# M_dulo_U_V_C_v_1_0.net
KiCad netlist of a schematic drawn in EAGLE
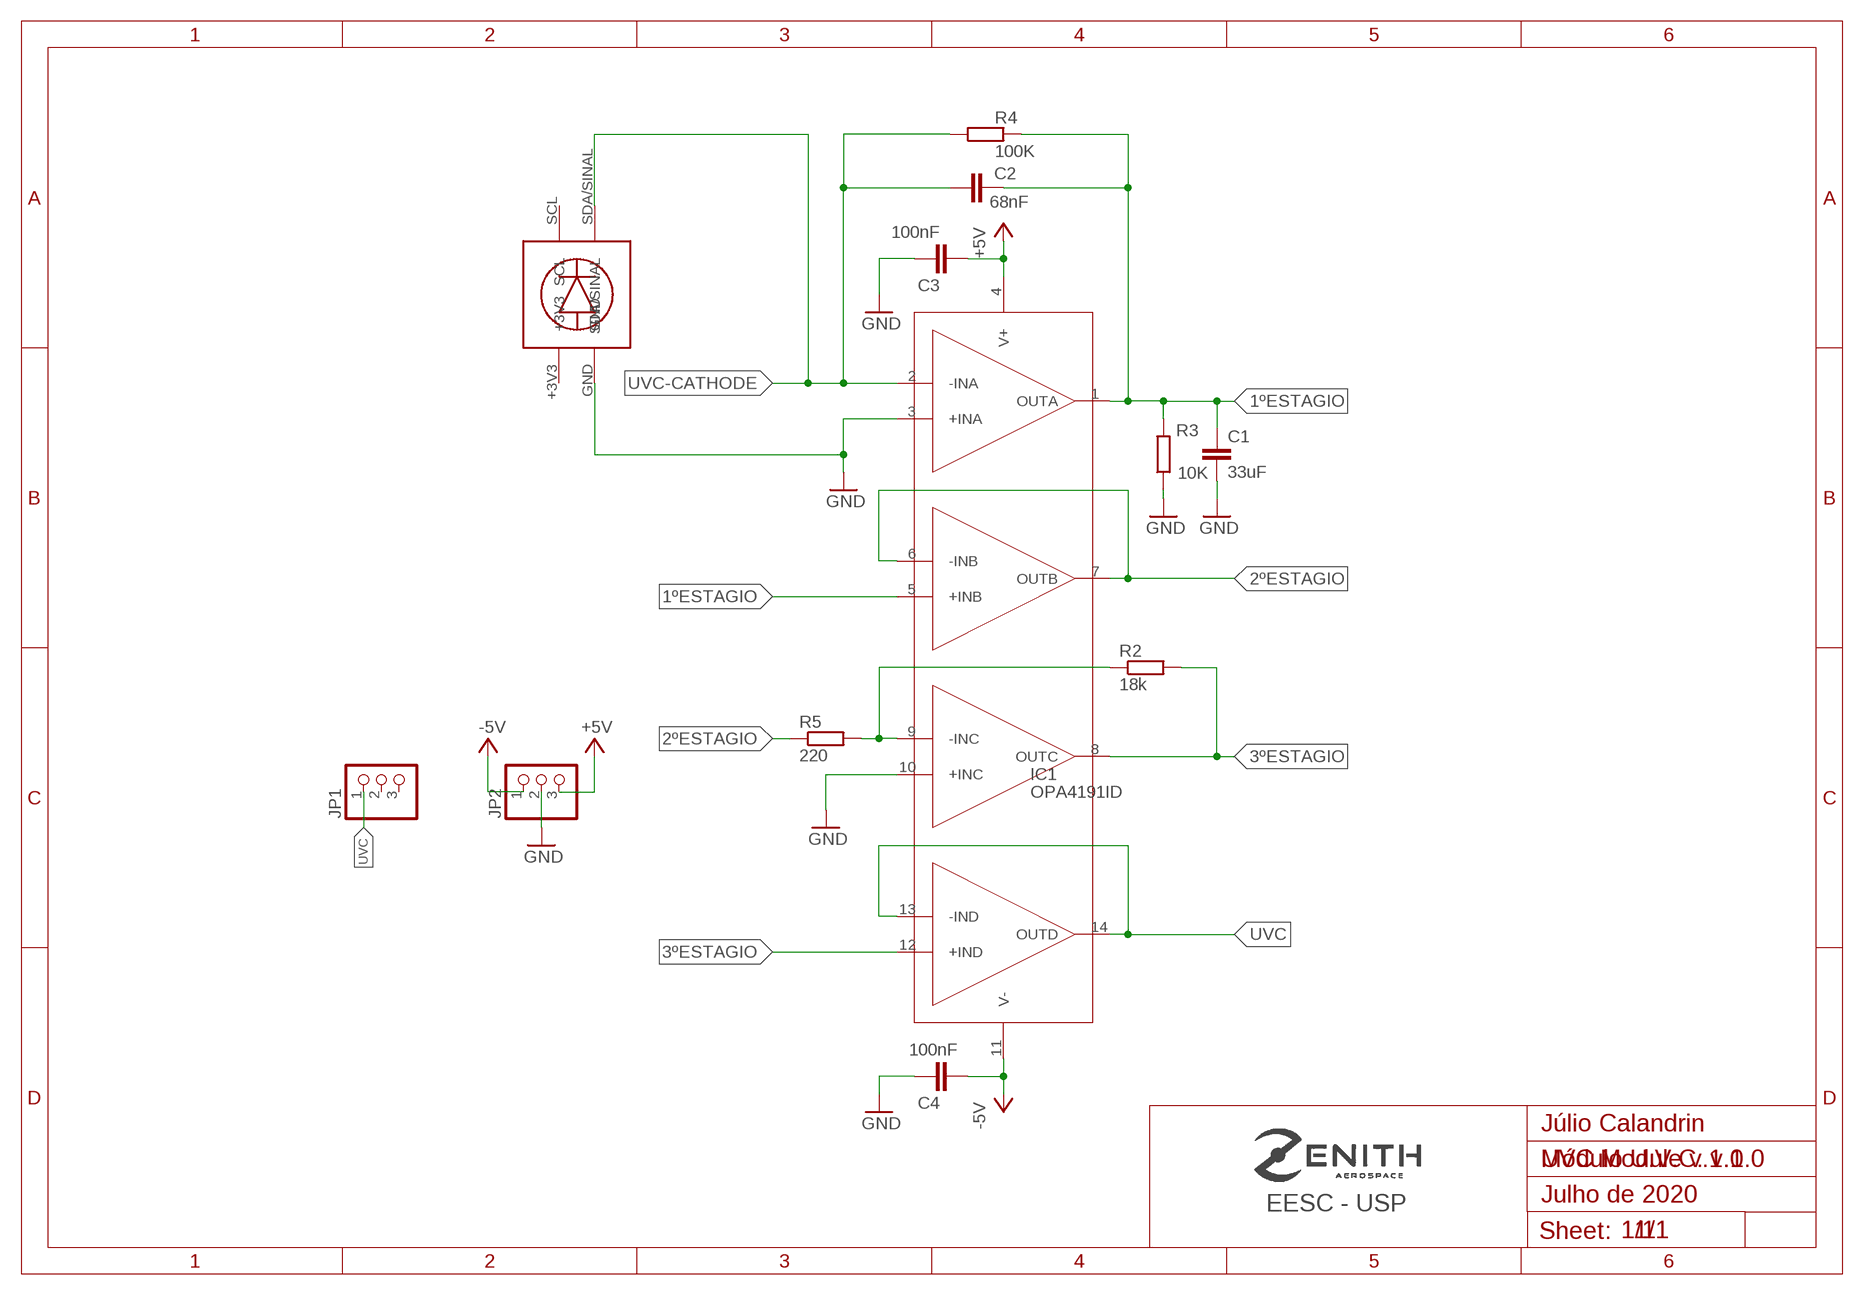
[diagram p0: schematic, sheet 1]

(export (version "E")
  (design (tool "Eeschema 10.0.6"))
  (components
    (comp (ref "C1")
      (value "33uF")
      (footprint "eagle-import:C0805")
      (libsource (lib "eagle-import") (part "C-EUC0805"))
    )
    (comp (ref "C2")
      (value "68nF")
      (footprint "eagle-import:C0805")
      (libsource (lib "eagle-import") (part "C-EUC0805"))
    )
    (comp (ref "C3")
      (value "100nF")
      (footprint "eagle-import:C0805")
      (libsource (lib "eagle-import") (part "C-EUC0805"))
    )
    (comp (ref "C4")
      (value "100nF")
      (footprint "eagle-import:C0805")
      (libsource (lib "eagle-import") (part "C-EUC0805"))
    )
    (comp (ref "IC1")
      (value "OPA4191ID")
      (footprint "eagle-import:D14_TEX")
      (fields (field (name "COPYRIGHT") "Copyright (C) 2018 Accelerated Designs. All rights reserved"))
      (libsource (lib "eagle-import") (part "OPA4191ID"))
    )
    (comp (ref "JP1")
      (value "PINHD-1X3")
      (footprint "eagle-import:1X03")
      (libsource (lib "eagle-import") (part "PINHD-1X3"))
    )
    (comp (ref "JP2")
      (value "PINHD-1X3")
      (footprint "eagle-import:1X03")
      (libsource (lib "eagle-import") (part "PINHD-1X3"))
    )
    (comp (ref "R2")
      (value "18k")
      (footprint "eagle-import:R0805")
      (libsource (lib "eagle-import") (part "R-EU_R0805"))
    )
    (comp (ref "R3")
      (value "10K")
      (footprint "eagle-import:R0805")
      (libsource (lib "eagle-import") (part "R-EU_R0805"))
    )
    (comp (ref "R4")
      (value "100K")
      (footprint "eagle-import:R0805")
      (libsource (lib "eagle-import") (part "R-EU_R0805"))
    )
    (comp (ref "R5")
      (value "220")
      (footprint "eagle-import:R0805")
      (libsource (lib "eagle-import") (part "R-EU_R0805"))
    )
    (comp (ref "U$3")
      (value "UNIVERSAL_BREAKOUT")
      (footprint "eagle-import:UNIVERSAL_PADS")
      (libsource (lib "eagle-import") (part "UNIVERSAL_BREAKOUT"))
    )
  )
  (nets
    (net (code "1") (name "+5V") (class "Default")
      (node (ref "C3") (pin "1") (pinfunction "1_1") (pintype "passive"))
      (node (ref "IC1") (pin "4") (pinfunction "V+_4") (pintype "power_in"))
      (node (ref "JP2") (pin "3") (pinfunction "3_3") (pintype "passive"))
    )
    (net (code "2") (name "-5V") (class "Default")
      (node (ref "C4") (pin "1") (pinfunction "1_1") (pintype "passive"))
      (node (ref "IC1") (pin "11") (pinfunction "V-_11") (pintype "power_in"))
      (node (ref "JP2") (pin "1") (pinfunction "1_1") (pintype "passive"))
    )
    (net (code "3") (name "1ºESTAGIO") (class "Default")
      (node (ref "C1") (pin "1") (pinfunction "1_1") (pintype "passive"))
      (node (ref "C2") (pin "2") (pinfunction "2_2") (pintype "passive"))
      (node (ref "IC1") (pin "1") (pinfunction "OUTA_1") (pintype "output"))
      (node (ref "IC1") (pin "5") (pinfunction "+INB_5") (pintype "input"))
      (node (ref "R3") (pin "2") (pinfunction "2_2") (pintype "passive"))
      (node (ref "R4") (pin "2") (pinfunction "2_2") (pintype "passive"))
    )
    (net (code "4") (name "2ºESTAGIO") (class "Default")
      (node (ref "IC1") (pin "6") (pinfunction "-INB_6") (pintype "passive"))
      (node (ref "IC1") (pin "7") (pinfunction "OUTB_7") (pintype "output"))
      (node (ref "R5") (pin "1") (pinfunction "1_1") (pintype "passive"))
    )
    (net (code "5") (name "3ºESTAGIO") (class "Default")
      (node (ref "IC1") (pin "12") (pinfunction "+IND_12") (pintype "input"))
      (node (ref "IC1") (pin "8") (pinfunction "OUTC_8") (pintype "output"))
      (node (ref "R2") (pin "2") (pinfunction "2_2") (pintype "passive"))
    )
    (net (code "6") (name "GND") (class "Default")
      (node (ref "C1") (pin "2") (pinfunction "2_2") (pintype "passive"))
      (node (ref "C3") (pin "2") (pinfunction "2_2") (pintype "passive"))
      (node (ref "C4") (pin "2") (pinfunction "2_2") (pintype "passive"))
      (node (ref "IC1") (pin "10") (pinfunction "+INC_10") (pintype "input"))
      (node (ref "IC1") (pin "3") (pinfunction "+INA_3") (pintype "input"))
      (node (ref "JP2") (pin "2") (pinfunction "2_2") (pintype "passive"))
      (node (ref "R3") (pin "1") (pinfunction "1_1") (pintype "passive"))
      (node (ref "U$3") (pin "GND") (pinfunction "GND_GND") (pintype "bidirectional"))
    )
    (net (code "7") (name "Net-(IC1--INC)") (class "Default")
      (node (ref "IC1") (pin "9") (pinfunction "-INC_9") (pintype "input"))
      (node (ref "R2") (pin "1") (pinfunction "1_1") (pintype "passive"))
      (node (ref "R5") (pin "2") (pinfunction "2_2") (pintype "passive"))
    )
    (net (code "8") (name "UVC") (class "Default")
      (node (ref "IC1") (pin "13") (pinfunction "-IND_13") (pintype "input"))
      (node (ref "IC1") (pin "14") (pinfunction "OUTD_14") (pintype "output"))
      (node (ref "JP1") (pin "1") (pinfunction "1_1") (pintype "passive"))
    )
    (net (code "9") (name "UVC-CATHODE") (class "Default")
      (node (ref "C2") (pin "1") (pinfunction "1_1") (pintype "passive"))
      (node (ref "IC1") (pin "2") (pinfunction "-INA_2") (pintype "passive"))
      (node (ref "R4") (pin "1") (pinfunction "1_1") (pintype "passive"))
      (node (ref "U$3") (pin "SDA/SINAL") (pinfunction "SDA/SINAL_SDA/SINAL") (pintype "bidirectional"))
    )
    (net (code "10") (name "unconnected-(JP1-Pad2)") (class "Default")
      (node (ref "JP1") (pin "2") (pinfunction "2_2") (pintype "passive"))
    )
    (net (code "11") (name "unconnected-(JP1-Pad3)") (class "Default")
      (node (ref "JP1") (pin "3") (pinfunction "3_3") (pintype "passive"))
    )
    (net (code "12") (name "unconnected-(U$3-Pad+3V3)") (class "Default")
      (node (ref "U$3") (pin "+3V3") (pinfunction "+3V3_+3V3") (pintype "bidirectional"))
    )
    (net (code "13") (name "unconnected-(U$3-PadSCL)") (class "Default")
      (node (ref "U$3") (pin "SCL") (pinfunction "SCL_SCL") (pintype "bidirectional"))
    )
  )
)
